# ADC.net
KiCad netlist of a schematic drawn in Altium Designer
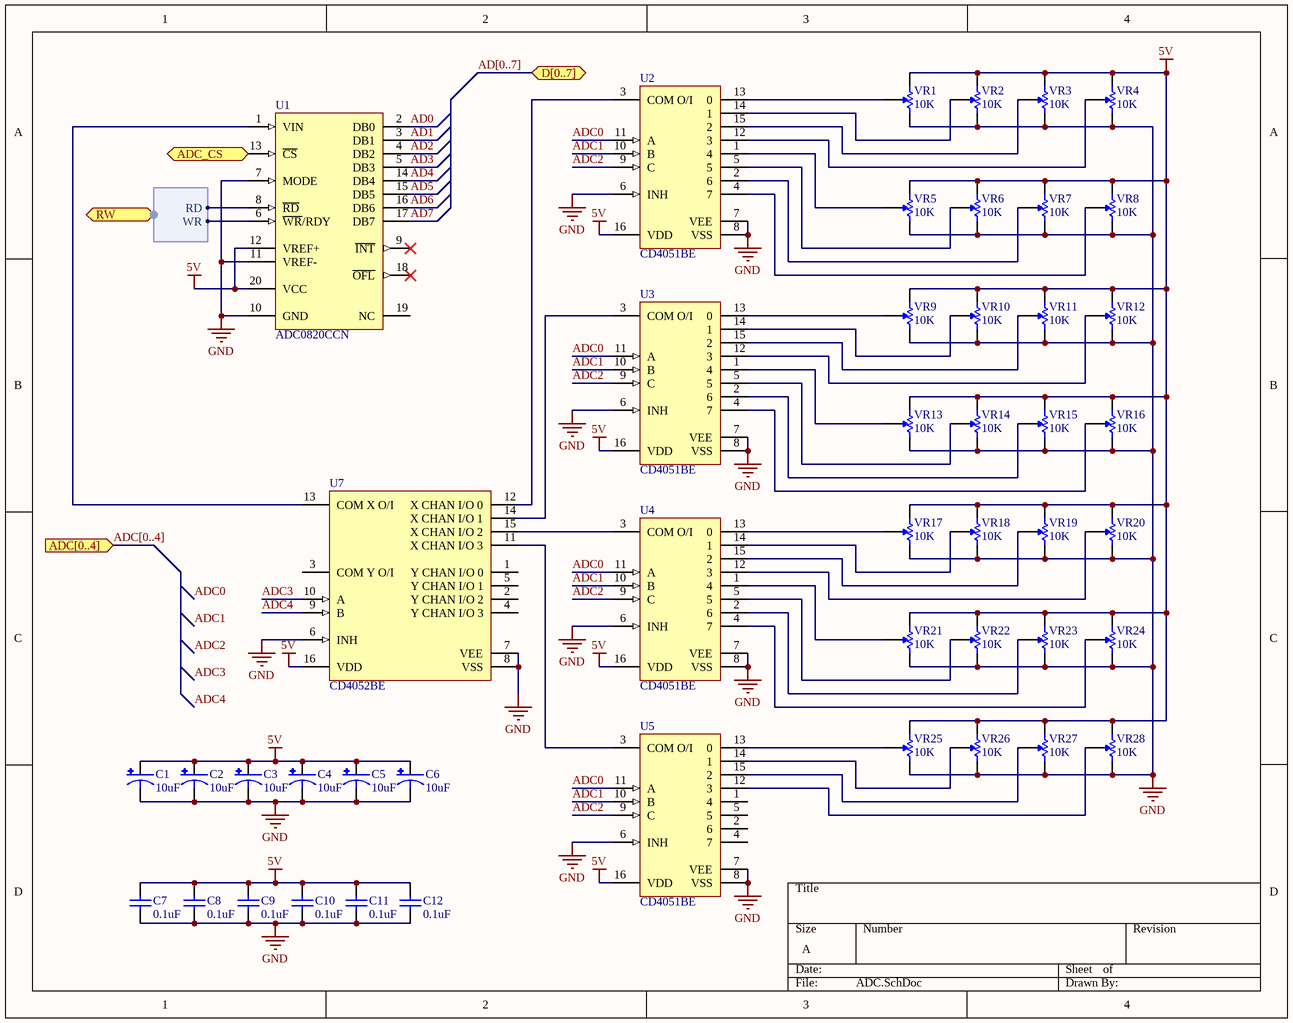
[diagram p0: ADC.SchDoc]

(export (version "E")
  (design (tool "Eeschema 10.0.6"))
  (components
    (comp (ref "C1")
      (value "10uF")
      (footprint "CPOL-RADIAL")
      (libsource (lib "Components") (part "PolarizedCap"))
    )
    (comp (ref "C2")
      (value "10uF")
      (footprint "CPOL-RADIAL")
      (libsource (lib "Components") (part "PolarizedCap"))
    )
    (comp (ref "C3")
      (value "10uF")
      (footprint "CPOL-RADIAL")
      (libsource (lib "Components") (part "PolarizedCap"))
    )
    (comp (ref "C4")
      (value "10uF")
      (footprint "CPOL-RADIAL")
      (libsource (lib "Components") (part "PolarizedCap"))
    )
    (comp (ref "C5")
      (value "10uF")
      (footprint "CPOL-RADIAL")
      (libsource (lib "Components") (part "PolarizedCap"))
    )
    (comp (ref "C6")
      (value "10uF")
      (footprint "CPOL-RADIAL")
      (libsource (lib "Components") (part "PolarizedCap"))
    )
    (comp (ref "C7") (value "0.1uF") (footprint "CAP-PTH") (libsource (lib "Components") (part "Cap")))
    (comp (ref "C8") (value "0.1uF") (footprint "CAP-PTH") (libsource (lib "Components") (part "Cap")))
    (comp (ref "C9") (value "0.1uF") (footprint "CAP-PTH") (libsource (lib "Components") (part "Cap")))
    (comp (ref "C10") (value "0.1uF") (footprint "CAP-PTH") (libsource (lib "Components") (part "Cap")))
    (comp (ref "C11") (value "0.1uF") (footprint "CAP-PTH") (libsource (lib "Components") (part "Cap")))
    (comp (ref "C12") (value "0.1uF") (footprint "CAP-PTH") (libsource (lib "Components") (part "Cap")))
    (comp (ref "U1")
      (value "ADC0820CCN")
      (footprint "N20A")
      (description "8-Bit High Speed uP Compatible A/D Converter with Track/Hold Function, 20-pin MDIP")
      (fields (field (name "MANUFACTURER") "National Semiconductor"))
      (libsource (lib "Altium Content Vault") (part "CON-ADC-ADC0820BCWM"))
    )
    (comp (ref "U2")
      (value "CD4051BE")
      (footprint "N0016A")
      (description "CMOS Single 8-Channel Analog Multiplexer/Demultiplexer with Logic-Level Conversion, N0016A, TUBE")
      (fields
        (field (name "GENERIC PART NUMBER") "CD4051B")
        (field (name "MANUFACTURER") "Texas Instruments")
      )
      (libsource (lib "Altium Content Vault") (part "TI-CD4051B-16"))
    )
    (comp (ref "U3")
      (value "CD4051BE")
      (footprint "N0016A")
      (description "CMOS Single 8-Channel Analog Multiplexer/Demultiplexer with Logic-Level Conversion, N0016A, TUBE")
      (fields
        (field (name "GENERIC PART NUMBER") "CD4051B")
        (field (name "MANUFACTURER") "Texas Instruments")
      )
      (libsource (lib "Altium Content Vault") (part "TI-CD4051B-16"))
    )
    (comp (ref "U4")
      (value "CD4051BE")
      (footprint "N0016A")
      (description "CMOS Single 8-Channel Analog Multiplexer/Demultiplexer with Logic-Level Conversion, N0016A, TUBE")
      (fields
        (field (name "GENERIC PART NUMBER") "CD4051B")
        (field (name "MANUFACTURER") "Texas Instruments")
      )
      (libsource (lib "Altium Content Vault") (part "TI-CD4051B-16"))
    )
    (comp (ref "U5")
      (value "CD4051BE")
      (footprint "N0016A")
      (description "CMOS Single 8-Channel Analog Multiplexer/Demultiplexer with Logic-Level Conversion, N0016A, TUBE")
      (fields
        (field (name "GENERIC PART NUMBER") "CD4051B")
        (field (name "MANUFACTURER") "Texas Instruments")
      )
      (libsource (lib "Altium Content Vault") (part "TI-CD4051B-16"))
    )
    (comp (ref "U7")
      (value "CD4052BE")
      (footprint "N0016A")
      (fields
        (field (name "GENERIC PART NUMBER") "CD4052B")
        (field (name "MANUFACTURER") "Texas Instruments")
      )
      (libsource (lib "Altium Content Vault") (part "TI-CD4052B-16"))
    )
    (comp (ref "VR1")
      (value "10K")
      (footprint "LINEAR_POT")
      (libsource (lib "Components") (part "LinearPot"))
    )
    (comp (ref "VR2")
      (value "10K")
      (footprint "LINEAR_POT")
      (libsource (lib "Components") (part "LinearPot"))
    )
    (comp (ref "VR3")
      (value "10K")
      (footprint "LINEAR_POT")
      (libsource (lib "Components") (part "LinearPot"))
    )
    (comp (ref "VR4")
      (value "10K")
      (footprint "LINEAR_POT")
      (libsource (lib "Components") (part "LinearPot"))
    )
    (comp (ref "VR5")
      (value "10K")
      (footprint "LINEAR_POT")
      (libsource (lib "Components") (part "LinearPot"))
    )
    (comp (ref "VR6")
      (value "10K")
      (footprint "LINEAR_POT")
      (libsource (lib "Components") (part "LinearPot"))
    )
    (comp (ref "VR7")
      (value "10K")
      (footprint "LINEAR_POT")
      (libsource (lib "Components") (part "LinearPot"))
    )
    (comp (ref "VR8")
      (value "10K")
      (footprint "LINEAR_POT")
      (libsource (lib "Components") (part "LinearPot"))
    )
    (comp (ref "VR9")
      (value "10K")
      (footprint "LINEAR_POT")
      (libsource (lib "Components") (part "LinearPot"))
    )
    (comp (ref "VR10")
      (value "10K")
      (footprint "LINEAR_POT")
      (libsource (lib "Components") (part "LinearPot"))
    )
    (comp (ref "VR11")
      (value "10K")
      (footprint "LINEAR_POT")
      (libsource (lib "Components") (part "LinearPot"))
    )
    (comp (ref "VR12")
      (value "10K")
      (footprint "LINEAR_POT")
      (libsource (lib "Components") (part "LinearPot"))
    )
    (comp (ref "VR13")
      (value "10K")
      (footprint "LINEAR_POT")
      (libsource (lib "Components") (part "LinearPot"))
    )
    (comp (ref "VR14")
      (value "10K")
      (footprint "LINEAR_POT")
      (libsource (lib "Components") (part "LinearPot"))
    )
    (comp (ref "VR15")
      (value "10K")
      (footprint "LINEAR_POT")
      (libsource (lib "Components") (part "LinearPot"))
    )
    (comp (ref "VR16")
      (value "10K")
      (footprint "LINEAR_POT")
      (libsource (lib "Components") (part "LinearPot"))
    )
    (comp (ref "VR17")
      (value "10K")
      (footprint "LINEAR_POT")
      (libsource (lib "Components") (part "LinearPot"))
    )
    (comp (ref "VR18")
      (value "10K")
      (footprint "LINEAR_POT")
      (libsource (lib "Components") (part "LinearPot"))
    )
    (comp (ref "VR19")
      (value "10K")
      (footprint "LINEAR_POT")
      (libsource (lib "Components") (part "LinearPot"))
    )
    (comp (ref "VR20")
      (value "10K")
      (footprint "LINEAR_POT")
      (libsource (lib "Components") (part "LinearPot"))
    )
    (comp (ref "VR21")
      (value "10K")
      (footprint "LINEAR_POT")
      (libsource (lib "Components") (part "LinearPot"))
    )
    (comp (ref "VR22")
      (value "10K")
      (footprint "LINEAR_POT")
      (libsource (lib "Components") (part "LinearPot"))
    )
    (comp (ref "VR23")
      (value "10K")
      (footprint "LINEAR_POT")
      (libsource (lib "Components") (part "LinearPot"))
    )
    (comp (ref "VR24")
      (value "10K")
      (footprint "LINEAR_POT")
      (libsource (lib "Components") (part "LinearPot"))
    )
    (comp (ref "VR25")
      (value "10K")
      (footprint "ROTARY_POT")
      (libsource (lib "Components") (part "RotaryPot"))
    )
    (comp (ref "VR26")
      (value "10K")
      (footprint "ROTARY_POT")
      (libsource (lib "Components") (part "RotaryPot"))
    )
    (comp (ref "VR27")
      (value "10K")
      (footprint "ROTARY_POT")
      (libsource (lib "Components") (part "RotaryPot"))
    )
    (comp (ref "VR28")
      (value "10K")
      (footprint "ROTARY_POT")
      (libsource (lib "Components") (part "RotaryPot"))
    )
  )
  (nets
    (net (code "2") (name "/AD0") (class "Default")
      (node (ref "U1") (pin "2") (pinfunction "DB0_2") (pintype "tri_state"))
    )
    (net (code "3") (name "/AD1") (class "Default")
      (node (ref "U1") (pin "3") (pinfunction "DB1_3") (pintype "tri_state"))
    )
    (net (code "4") (name "/AD2") (class "Default")
      (node (ref "U1") (pin "4") (pinfunction "DB2_4") (pintype "tri_state"))
    )
    (net (code "5") (name "/AD3") (class "Default")
      (node (ref "U1") (pin "5") (pinfunction "DB3_5") (pintype "tri_state"))
    )
    (net (code "6") (name "/AD4") (class "Default")
      (node (ref "U1") (pin "14") (pinfunction "DB4_14") (pintype "tri_state"))
    )
    (net (code "7") (name "/AD5") (class "Default")
      (node (ref "U1") (pin "15") (pinfunction "DB5_15") (pintype "tri_state"))
    )
    (net (code "8") (name "/AD6") (class "Default")
      (node (ref "U1") (pin "16") (pinfunction "DB6_16") (pintype "tri_state"))
    )
    (net (code "9") (name "/AD7") (class "Default")
      (node (ref "U1") (pin "17") (pinfunction "DB7_17") (pintype "tri_state"))
    )
    (net (code "10") (name "/ADC0") (class "Default")
      (node (ref "U2") (pin "11") (pinfunction "A_11") (pintype "input"))
      (node (ref "U3") (pin "11") (pinfunction "A_11") (pintype "input"))
      (node (ref "U4") (pin "11") (pinfunction "A_11") (pintype "input"))
      (node (ref "U5") (pin "11") (pinfunction "A_11") (pintype "input"))
    )
    (net (code "11") (name "/ADC1") (class "Default")
      (node (ref "U2") (pin "10") (pinfunction "B_10") (pintype "input"))
      (node (ref "U3") (pin "10") (pinfunction "B_10") (pintype "input"))
      (node (ref "U4") (pin "10") (pinfunction "B_10") (pintype "input"))
      (node (ref "U5") (pin "10") (pinfunction "B_10") (pintype "input"))
    )
    (net (code "12") (name "/ADC2") (class "Default")
      (node (ref "U2") (pin "9") (pinfunction "C_9") (pintype "input"))
      (node (ref "U3") (pin "9") (pinfunction "C_9") (pintype "input"))
      (node (ref "U4") (pin "9") (pinfunction "C_9") (pintype "input"))
      (node (ref "U5") (pin "9") (pinfunction "C_9") (pintype "input"))
    )
    (net (code "13") (name "/ADC3") (class "Default")
      (node (ref "U7") (pin "10") (pinfunction "A_10") (pintype "input"))
    )
    (net (code "14") (name "/ADC4") (class "Default")
      (node (ref "U7") (pin "9") (pinfunction "B_9") (pintype "input"))
    )
    (net (code "16") (name "/ADC_CS") (class "Default")
      (node (ref "U1") (pin "13") (pinfunction "~{CS}_13") (pintype "input"))
    )
    (net (code "18") (name "/RD") (class "Default")
      (node (ref "U1") (pin "8") (pinfunction "~{RD}_8") (pintype "input"))
    )
    (net (code "19") (name "/WR") (class "Default")
      (node (ref "U1") (pin "6") (pinfunction "~{WR}/RDY_6") (pintype "input"))
    )
    (net (code "21") (name "5V") (class "Default")
      (node (ref "C1") (pin "1") (pinfunction "+_1") (pintype "passive"))
      (node (ref "C10") (pin "1") (pinfunction "1_1") (pintype "passive"))
      (node (ref "C11") (pin "1") (pinfunction "1_1") (pintype "passive"))
      (node (ref "C12") (pin "1") (pinfunction "1_1") (pintype "passive"))
      (node (ref "C2") (pin "1") (pinfunction "+_1") (pintype "passive"))
      (node (ref "C3") (pin "1") (pinfunction "+_1") (pintype "passive"))
      (node (ref "C4") (pin "1") (pinfunction "+_1") (pintype "passive"))
      (node (ref "C5") (pin "1") (pinfunction "+_1") (pintype "passive"))
      (node (ref "C6") (pin "1") (pinfunction "+_1") (pintype "passive"))
      (node (ref "C7") (pin "1") (pinfunction "1_1") (pintype "passive"))
      (node (ref "C8") (pin "1") (pinfunction "1_1") (pintype "passive"))
      (node (ref "C9") (pin "1") (pinfunction "1_1") (pintype "passive"))
      (node (ref "U1") (pin "12") (pinfunction "VREF+_12") (pintype "power_in"))
      (node (ref "U1") (pin "20") (pinfunction "VCC_20") (pintype "power_in"))
      (node (ref "U2") (pin "16") (pinfunction "VDD_16") (pintype "power_in"))
      (node (ref "U3") (pin "16") (pinfunction "VDD_16") (pintype "power_in"))
      (node (ref "U4") (pin "16") (pinfunction "VDD_16") (pintype "power_in"))
      (node (ref "U5") (pin "16") (pinfunction "VDD_16") (pintype "power_in"))
      (node (ref "U7") (pin "16") (pinfunction "VDD_16") (pintype "power_in"))
      (node (ref "VR1") (pin "1") (pinfunction "1_1") (pintype "passive"))
      (node (ref "VR10") (pin "1") (pinfunction "1_1") (pintype "passive"))
      (node (ref "VR11") (pin "1") (pinfunction "1_1") (pintype "passive"))
      (node (ref "VR12") (pin "1") (pinfunction "1_1") (pintype "passive"))
      (node (ref "VR13") (pin "1") (pinfunction "1_1") (pintype "passive"))
      (node (ref "VR14") (pin "1") (pinfunction "1_1") (pintype "passive"))
      (node (ref "VR15") (pin "1") (pinfunction "1_1") (pintype "passive"))
      (node (ref "VR16") (pin "1") (pinfunction "1_1") (pintype "passive"))
      (node (ref "VR17") (pin "1") (pinfunction "1_1") (pintype "passive"))
      (node (ref "VR18") (pin "1") (pinfunction "1_1") (pintype "passive"))
      (node (ref "VR19") (pin "1") (pinfunction "1_1") (pintype "passive"))
      (node (ref "VR2") (pin "1") (pinfunction "1_1") (pintype "passive"))
      (node (ref "VR20") (pin "1") (pinfunction "1_1") (pintype "passive"))
      (node (ref "VR21") (pin "1") (pinfunction "1_1") (pintype "passive"))
      (node (ref "VR22") (pin "1") (pinfunction "1_1") (pintype "passive"))
      (node (ref "VR23") (pin "1") (pinfunction "1_1") (pintype "passive"))
      (node (ref "VR24") (pin "1") (pinfunction "1_1") (pintype "passive"))
      (node (ref "VR25") (pin "1") (pinfunction "1_1") (pintype "passive"))
      (node (ref "VR26") (pin "1") (pinfunction "1_1") (pintype "passive"))
      (node (ref "VR27") (pin "1") (pinfunction "1_1") (pintype "passive"))
      (node (ref "VR28") (pin "1") (pinfunction "1_1") (pintype "passive"))
      (node (ref "VR3") (pin "1") (pinfunction "1_1") (pintype "passive"))
      (node (ref "VR4") (pin "1") (pinfunction "1_1") (pintype "passive"))
      (node (ref "VR5") (pin "1") (pinfunction "1_1") (pintype "passive"))
      (node (ref "VR6") (pin "1") (pinfunction "1_1") (pintype "passive"))
      (node (ref "VR7") (pin "1") (pinfunction "1_1") (pintype "passive"))
      (node (ref "VR8") (pin "1") (pinfunction "1_1") (pintype "passive"))
      (node (ref "VR9") (pin "1") (pinfunction "1_1") (pintype "passive"))
    )
    (net (code "22") (name "GND") (class "Default")
      (node (ref "C1") (pin "2") (pinfunction "-_2") (pintype "passive"))
      (node (ref "C10") (pin "2") (pinfunction "2_2") (pintype "passive"))
      (node (ref "C11") (pin "2") (pinfunction "2_2") (pintype "passive"))
      (node (ref "C12") (pin "2") (pinfunction "2_2") (pintype "passive"))
      (node (ref "C2") (pin "2") (pinfunction "-_2") (pintype "passive"))
      (node (ref "C3") (pin "2") (pinfunction "-_2") (pintype "passive"))
      (node (ref "C4") (pin "2") (pinfunction "-_2") (pintype "passive"))
      (node (ref "C5") (pin "2") (pinfunction "-_2") (pintype "passive"))
      (node (ref "C6") (pin "2") (pinfunction "-_2") (pintype "passive"))
      (node (ref "C7") (pin "2") (pinfunction "2_2") (pintype "passive"))
      (node (ref "C8") (pin "2") (pinfunction "2_2") (pintype "passive"))
      (node (ref "C9") (pin "2") (pinfunction "2_2") (pintype "passive"))
      (node (ref "U1") (pin "10") (pinfunction "GND_10") (pintype "power_in"))
      (node (ref "U1") (pin "11") (pinfunction "VREF-_11") (pintype "power_in"))
      (node (ref "U1") (pin "7") (pinfunction "MODE_7") (pintype "input"))
      (node (ref "U2") (pin "6") (pinfunction "INH_6") (pintype "input"))
      (node (ref "U2") (pin "7") (pinfunction "VEE_7") (pintype "power_in"))
      (node (ref "U2") (pin "8") (pinfunction "VSS_8") (pintype "power_in"))
      (node (ref "U3") (pin "6") (pinfunction "INH_6") (pintype "input"))
      (node (ref "U3") (pin "7") (pinfunction "VEE_7") (pintype "power_in"))
      (node (ref "U3") (pin "8") (pinfunction "VSS_8") (pintype "power_in"))
      (node (ref "U4") (pin "6") (pinfunction "INH_6") (pintype "input"))
      (node (ref "U4") (pin "7") (pinfunction "VEE_7") (pintype "power_in"))
      (node (ref "U4") (pin "8") (pinfunction "VSS_8") (pintype "power_in"))
      (node (ref "U5") (pin "6") (pinfunction "INH_6") (pintype "input"))
      (node (ref "U5") (pin "7") (pinfunction "VEE_7") (pintype "power_in"))
      (node (ref "U5") (pin "8") (pinfunction "VSS_8") (pintype "power_in"))
      (node (ref "U7") (pin "6") (pinfunction "INH_6") (pintype "input"))
      (node (ref "U7") (pin "7") (pinfunction "VEE_7") (pintype "power_in"))
      (node (ref "U7") (pin "8") (pinfunction "VSS_8") (pintype "power_in"))
      (node (ref "VR1") (pin "3") (pinfunction "3_3") (pintype "passive"))
      (node (ref "VR10") (pin "3") (pinfunction "3_3") (pintype "passive"))
      (node (ref "VR11") (pin "3") (pinfunction "3_3") (pintype "passive"))
      (node (ref "VR12") (pin "3") (pinfunction "3_3") (pintype "passive"))
      (node (ref "VR13") (pin "3") (pinfunction "3_3") (pintype "passive"))
      (node (ref "VR14") (pin "3") (pinfunction "3_3") (pintype "passive"))
      (node (ref "VR15") (pin "3") (pinfunction "3_3") (pintype "passive"))
      (node (ref "VR16") (pin "3") (pinfunction "3_3") (pintype "passive"))
      (node (ref "VR17") (pin "3") (pinfunction "3_3") (pintype "passive"))
      (node (ref "VR18") (pin "3") (pinfunction "3_3") (pintype "passive"))
      (node (ref "VR19") (pin "3") (pinfunction "3_3") (pintype "passive"))
      (node (ref "VR2") (pin "3") (pinfunction "3_3") (pintype "passive"))
      (node (ref "VR20") (pin "3") (pinfunction "3_3") (pintype "passive"))
      (node (ref "VR21") (pin "3") (pinfunction "3_3") (pintype "passive"))
      (node (ref "VR22") (pin "3") (pinfunction "3_3") (pintype "passive"))
      (node (ref "VR23") (pin "3") (pinfunction "3_3") (pintype "passive"))
      (node (ref "VR24") (pin "3") (pinfunction "3_3") (pintype "passive"))
      (node (ref "VR25") (pin "3") (pinfunction "3_3") (pintype "passive"))
      (node (ref "VR26") (pin "3") (pinfunction "3_3") (pintype "passive"))
      (node (ref "VR27") (pin "3") (pinfunction "3_3") (pintype "passive"))
      (node (ref "VR28") (pin "3") (pinfunction "3_3") (pintype "passive"))
      (node (ref "VR3") (pin "3") (pinfunction "3_3") (pintype "passive"))
      (node (ref "VR4") (pin "3") (pinfunction "3_3") (pintype "passive"))
      (node (ref "VR5") (pin "3") (pinfunction "3_3") (pintype "passive"))
      (node (ref "VR6") (pin "3") (pinfunction "3_3") (pintype "passive"))
      (node (ref "VR7") (pin "3") (pinfunction "3_3") (pintype "passive"))
      (node (ref "VR8") (pin "3") (pinfunction "3_3") (pintype "passive"))
      (node (ref "VR9") (pin "3") (pinfunction "3_3") (pintype "passive"))
    )
    (net (code "23") (name "Net-(U1-VIN)") (class "Default")
      (node (ref "U1") (pin "1") (pinfunction "VIN_1") (pintype "input"))
      (node (ref "U7") (pin "13") (pinfunction "COM_X_O/I_13") (pintype "passive"))
    )
    (net (code "24") (name "Net-(U2-0)") (class "Default")
      (node (ref "U2") (pin "13") (pinfunction "0_13") (pintype "passive"))
      (node (ref "VR1") (pin "2") (pinfunction "2_2") (pintype "passive"))
    )
    (net (code "25") (name "Net-(U2-1)") (class "Default")
      (node (ref "U2") (pin "14") (pinfunction "1_14") (pintype "passive"))
      (node (ref "VR2") (pin "2") (pinfunction "2_2") (pintype "passive"))
    )
    (net (code "26") (name "Net-(U2-2)") (class "Default")
      (node (ref "U2") (pin "15") (pinfunction "2_15") (pintype "passive"))
      (node (ref "VR3") (pin "2") (pinfunction "2_2") (pintype "passive"))
    )
    (net (code "27") (name "Net-(U2-3)") (class "Default")
      (node (ref "U2") (pin "12") (pinfunction "3_12") (pintype "passive"))
      (node (ref "VR4") (pin "2") (pinfunction "2_2") (pintype "passive"))
    )
    (net (code "28") (name "Net-(U2-4)") (class "Default")
      (node (ref "U2") (pin "1") (pinfunction "4_1") (pintype "passive"))
      (node (ref "VR5") (pin "2") (pinfunction "2_2") (pintype "passive"))
    )
    (net (code "29") (name "Net-(U2-6)") (class "Default")
      (node (ref "U2") (pin "2") (pinfunction "6_2") (pintype "passive"))
      (node (ref "VR7") (pin "2") (pinfunction "2_2") (pintype "passive"))
    )
    (net (code "30") (name "Net-(U2-7)") (class "Default")
      (node (ref "U2") (pin "4") (pinfunction "7_4") (pintype "passive"))
      (node (ref "VR8") (pin "2") (pinfunction "2_2") (pintype "passive"))
    )
    (net (code "31") (name "Net-(U2-COM_O{slash}I)") (class "Default")
      (node (ref "U2") (pin "3") (pinfunction "COM_O/I_3") (pintype "passive"))
      (node (ref "U7") (pin "12") (pinfunction "X_CHAN_I/O_0_12") (pintype "passive"))
    )
    (net (code "32") (name "Net-(U2-Pad5)") (class "Default")
      (node (ref "U2") (pin "5") (pinfunction "5_5") (pintype "passive"))
      (node (ref "VR6") (pin "2") (pinfunction "2_2") (pintype "passive"))
    )
    (net (code "33") (name "Net-(U3-0)") (class "Default")
      (node (ref "U3") (pin "13") (pinfunction "0_13") (pintype "passive"))
      (node (ref "VR9") (pin "2") (pinfunction "2_2") (pintype "passive"))
    )
    (net (code "34") (name "Net-(U3-1)") (class "Default")
      (node (ref "U3") (pin "14") (pinfunction "1_14") (pintype "passive"))
      (node (ref "VR10") (pin "2") (pinfunction "2_2") (pintype "passive"))
    )
    (net (code "35") (name "Net-(U3-2)") (class "Default")
      (node (ref "U3") (pin "15") (pinfunction "2_15") (pintype "passive"))
      (node (ref "VR11") (pin "2") (pinfunction "2_2") (pintype "passive"))
    )
    (net (code "36") (name "Net-(U3-3)") (class "Default")
      (node (ref "U3") (pin "12") (pinfunction "3_12") (pintype "passive"))
      (node (ref "VR12") (pin "2") (pinfunction "2_2") (pintype "passive"))
    )
    (net (code "37") (name "Net-(U3-4)") (class "Default")
      (node (ref "U3") (pin "1") (pinfunction "4_1") (pintype "passive"))
      (node (ref "VR13") (pin "2") (pinfunction "2_2") (pintype "passive"))
    )
    (net (code "38") (name "Net-(U3-6)") (class "Default")
      (node (ref "U3") (pin "2") (pinfunction "6_2") (pintype "passive"))
      (node (ref "VR15") (pin "2") (pinfunction "2_2") (pintype "passive"))
    )
    (net (code "39") (name "Net-(U3-7)") (class "Default")
      (node (ref "U3") (pin "4") (pinfunction "7_4") (pintype "passive"))
      (node (ref "VR16") (pin "2") (pinfunction "2_2") (pintype "passive"))
    )
    (net (code "40") (name "Net-(U3-COM_O{slash}I)") (class "Default")
      (node (ref "U3") (pin "3") (pinfunction "COM_O/I_3") (pintype "passive"))
      (node (ref "U7") (pin "14") (pinfunction "X_CHAN_I/O_1_14") (pintype "passive"))
    )
    (net (code "41") (name "Net-(U3-Pad5)") (class "Default")
      (node (ref "U3") (pin "5") (pinfunction "5_5") (pintype "passive"))
      (node (ref "VR14") (pin "2") (pinfunction "2_2") (pintype "passive"))
    )
    (net (code "42") (name "Net-(U4-0)") (class "Default")
      (node (ref "U4") (pin "13") (pinfunction "0_13") (pintype "passive"))
      (node (ref "VR17") (pin "2") (pinfunction "2_2") (pintype "passive"))
    )
    (net (code "43") (name "Net-(U4-1)") (class "Default")
      (node (ref "U4") (pin "14") (pinfunction "1_14") (pintype "passive"))
      (node (ref "VR18") (pin "2") (pinfunction "2_2") (pintype "passive"))
    )
    (net (code "44") (name "Net-(U4-2)") (class "Default")
      (node (ref "U4") (pin "15") (pinfunction "2_15") (pintype "passive"))
      (node (ref "VR19") (pin "2") (pinfunction "2_2") (pintype "passive"))
    )
    (net (code "45") (name "Net-(U4-3)") (class "Default")
      (node (ref "U4") (pin "12") (pinfunction "3_12") (pintype "passive"))
      (node (ref "VR20") (pin "2") (pinfunction "2_2") (pintype "passive"))
    )
    (net (code "46") (name "Net-(U4-4)") (class "Default")
      (node (ref "U4") (pin "1") (pinfunction "4_1") (pintype "passive"))
      (node (ref "VR21") (pin "2") (pinfunction "2_2") (pintype "passive"))
    )
    (net (code "47") (name "Net-(U4-6)") (class "Default")
      (node (ref "U4") (pin "2") (pinfunction "6_2") (pintype "passive"))
      (node (ref "VR23") (pin "2") (pinfunction "2_2") (pintype "passive"))
    )
    (net (code "48") (name "Net-(U4-7)") (class "Default")
      (node (ref "U4") (pin "4") (pinfunction "7_4") (pintype "passive"))
      (node (ref "VR24") (pin "2") (pinfunction "2_2") (pintype "passive"))
    )
    (net (code "49") (name "Net-(U4-COM_O{slash}I)") (class "Default")
      (node (ref "U4") (pin "3") (pinfunction "COM_O/I_3") (pintype "passive"))
      (node (ref "U7") (pin "15") (pinfunction "X_CHAN_I/O_2_15") (pintype "passive"))
    )
    (net (code "50") (name "Net-(U4-Pad5)") (class "Default")
      (node (ref "U4") (pin "5") (pinfunction "5_5") (pintype "passive"))
      (node (ref "VR22") (pin "2") (pinfunction "2_2") (pintype "passive"))
    )
    (net (code "51") (name "Net-(U5-0)") (class "Default")
      (node (ref "U5") (pin "13") (pinfunction "0_13") (pintype "passive"))
      (node (ref "VR25") (pin "2") (pinfunction "2_2") (pintype "passive"))
    )
    (net (code "52") (name "Net-(U5-1)") (class "Default")
      (node (ref "U5") (pin "14") (pinfunction "1_14") (pintype "passive"))
      (node (ref "VR26") (pin "2") (pinfunction "2_2") (pintype "passive"))
    )
    (net (code "53") (name "Net-(U5-2)") (class "Default")
      (node (ref "U5") (pin "15") (pinfunction "2_15") (pintype "passive"))
      (node (ref "VR27") (pin "2") (pinfunction "2_2") (pintype "passive"))
    )
    (net (code "54") (name "Net-(U5-3)") (class "Default")
      (node (ref "U5") (pin "12") (pinfunction "3_12") (pintype "passive"))
      (node (ref "VR28") (pin "2") (pinfunction "2_2") (pintype "passive"))
    )
    (net (code "55") (name "Net-(U5-COM_O{slash}I)") (class "Default")
      (node (ref "U5") (pin "3") (pinfunction "COM_O/I_3") (pintype "passive"))
      (node (ref "U7") (pin "11") (pinfunction "X_CHAN_I/O_3_11") (pintype "passive"))
    )
    (net (code "56") (name "unconnected-(U1-NC-Pad19)") (class "Default")
      (node (ref "U1") (pin "19") (pinfunction "NC_19") (pintype "passive"))
    )
    (net (code "57") (name "unconnected-(U1-~{INT}-Pad9)") (class "Default")
      (node (ref "U1") (pin "9") (pinfunction "~{INT}_9") (pintype "output+no_connect"))
    )
    (net (code "58") (name "unconnected-(U1-~{OFL}-Pad18)") (class "Default")
      (node (ref "U1") (pin "18") (pinfunction "~{OFL}_18") (pintype "output+no_connect"))
    )
    (net (code "59") (name "unconnected-(U5-4-Pad1)") (class "Default")
      (node (ref "U5") (pin "1") (pinfunction "4_1") (pintype "passive"))
    )
    (net (code "60") (name "unconnected-(U5-6-Pad2)") (class "Default")
      (node (ref "U5") (pin "2") (pinfunction "6_2") (pintype "passive"))
    )
    (net (code "61") (name "unconnected-(U5-7-Pad4)") (class "Default")
      (node (ref "U5") (pin "4") (pinfunction "7_4") (pintype "passive"))
    )
    (net (code "62") (name "unconnected-(U5-Pad5)") (class "Default")
      (node (ref "U5") (pin "5") (pinfunction "5_5") (pintype "passive"))
    )
    (net (code "63") (name "unconnected-(U7-COM_Y_O{slash}I-Pad3)") (class "Default")
      (node (ref "U7") (pin "3") (pinfunction "COM_Y_O/I_3") (pintype "passive"))
    )
    (net (code "64") (name "unconnected-(U7-Y_CHAN_I{slash}O_0-Pad1)") (class "Default")
      (node (ref "U7") (pin "1") (pinfunction "Y_CHAN_I/O_0_1") (pintype "passive"))
    )
    (net (code "65") (name "unconnected-(U7-Y_CHAN_I{slash}O_1-Pad5)") (class "Default")
      (node (ref "U7") (pin "5") (pinfunction "Y_CHAN_I/O_1_5") (pintype "passive"))
    )
    (net (code "66") (name "unconnected-(U7-Y_CHAN_I{slash}O_2-Pad2)") (class "Default")
      (node (ref "U7") (pin "2") (pinfunction "Y_CHAN_I/O_2_2") (pintype "passive"))
    )
    (net (code "67") (name "unconnected-(U7-Y_CHAN_I{slash}O_3-Pad4)") (class "Default")
      (node (ref "U7") (pin "4") (pinfunction "Y_CHAN_I/O_3_4") (pintype "passive"))
    )
  )
)
